# B104X.net
KiCad netlist of a schematic drawn in EAGLE
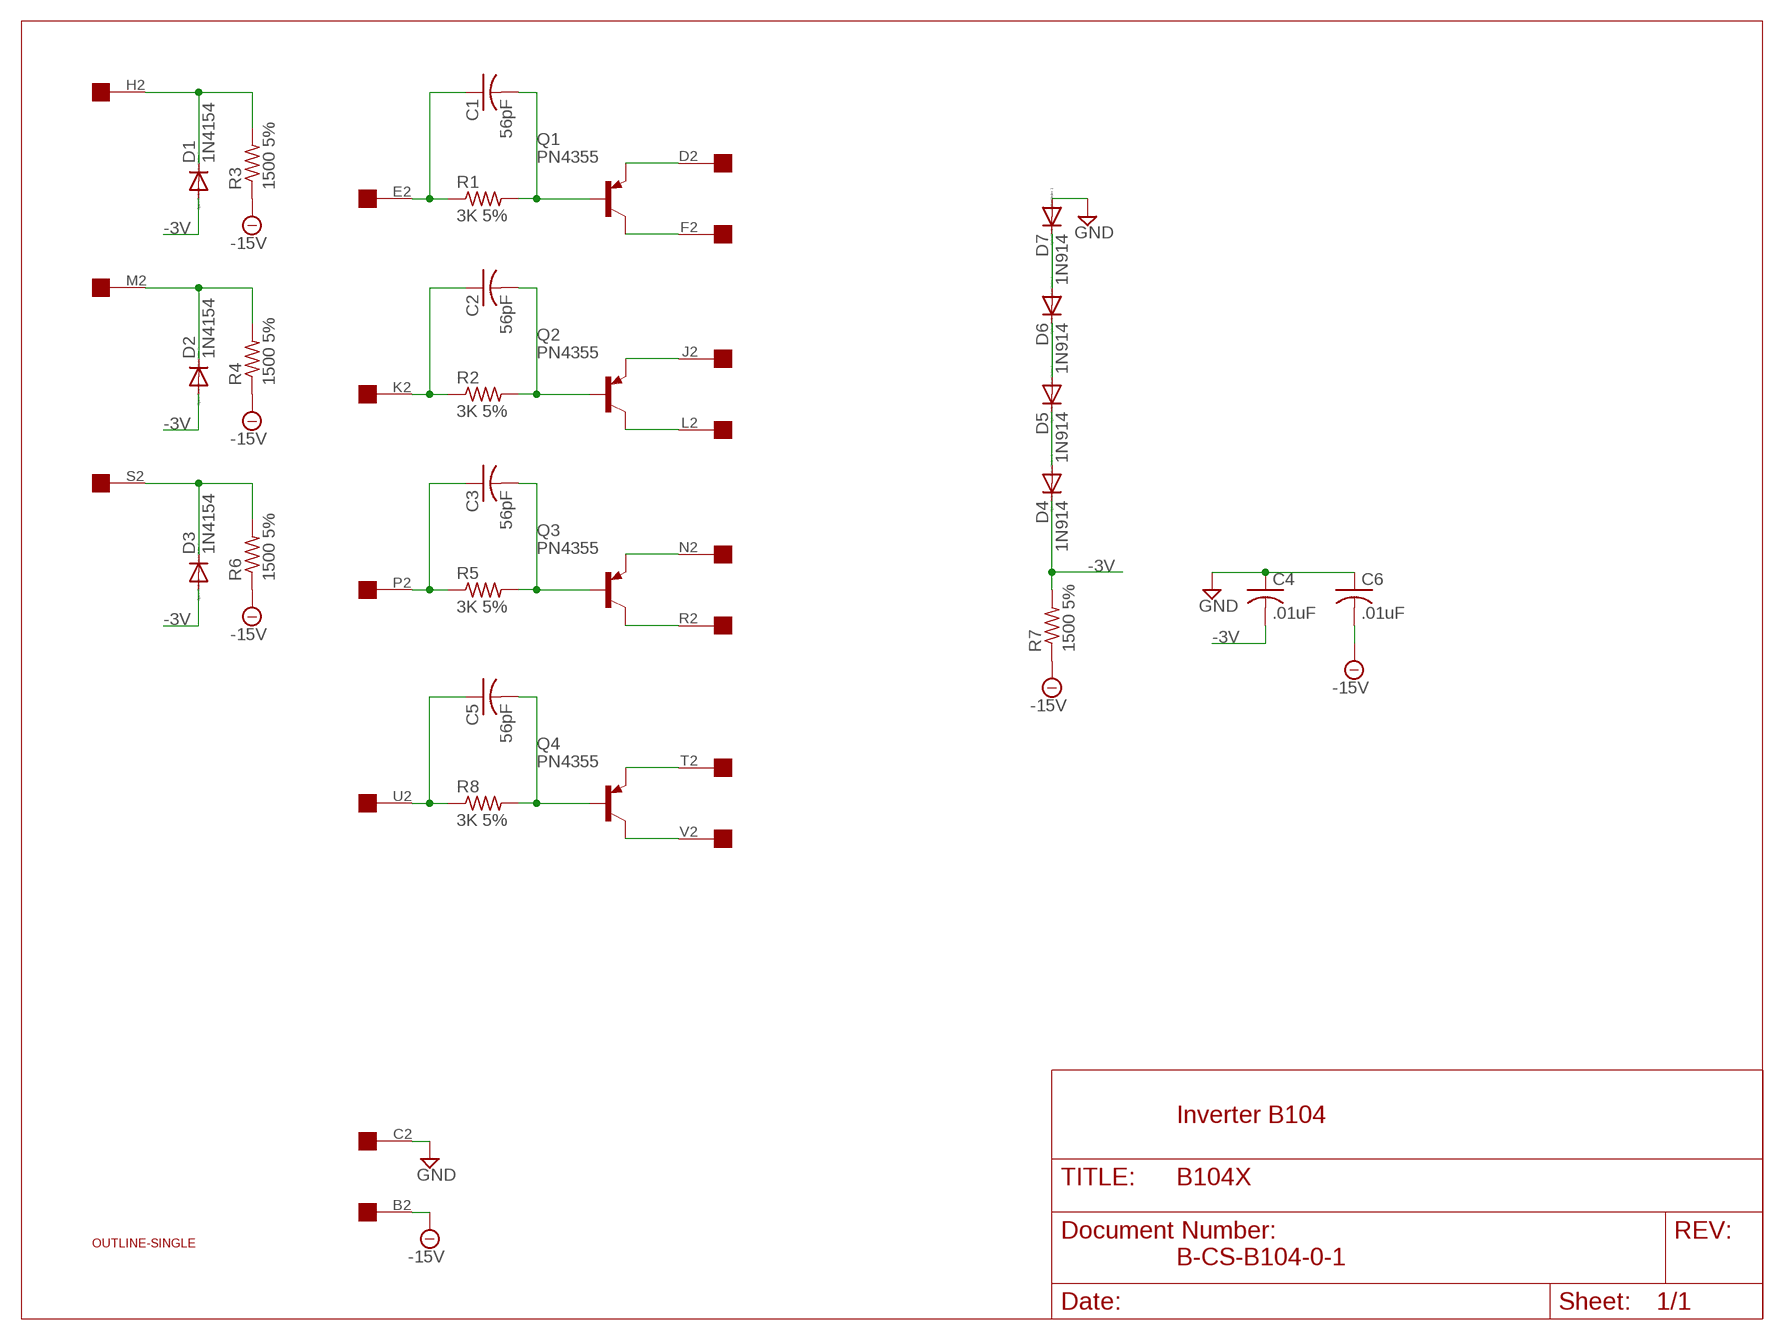
[diagram p0: schematic, sheet 1]

(export (version "E")
  (design (tool "Eeschema 10.0.6"))
  (components
    (comp (ref "C1")
      (value "56pF")
      (footprint "eagle-import:C075-032X103")
      (libsource (lib "eagle-import") (part "C-US075-032X103"))
    )
    (comp (ref "C2")
      (value "56pF")
      (footprint "eagle-import:C075-032X103")
      (libsource (lib "eagle-import") (part "C-US075-032X103"))
    )
    (comp (ref "C3")
      (value "56pF")
      (footprint "eagle-import:C075-032X103")
      (libsource (lib "eagle-import") (part "C-US075-032X103"))
    )
    (comp (ref "C4")
      (value ".01uF")
      (footprint "eagle-import:C050-025X075")
      (libsource (lib "eagle-import") (part "C-US050-025X075"))
    )
    (comp (ref "C5")
      (value "56pF")
      (footprint "eagle-import:C075-032X103")
      (libsource (lib "eagle-import") (part "C-US075-032X103"))
    )
    (comp (ref "C6")
      (value ".01uF")
      (footprint "eagle-import:C050-025X075")
      (libsource (lib "eagle-import") (part "C-US050-025X075"))
    )
    (comp (ref "D1")
      (value "1N4154")
      (footprint "eagle-import:DO35-10")
      (libsource (lib "eagle-import") (part "1N4148DO35-10"))
    )
    (comp (ref "D2")
      (value "1N4154")
      (footprint "eagle-import:DO35-10")
      (libsource (lib "eagle-import") (part "1N4148DO35-10"))
    )
    (comp (ref "D3")
      (value "1N4154")
      (footprint "eagle-import:DO35-10")
      (libsource (lib "eagle-import") (part "1N4148DO35-10"))
    )
    (comp (ref "D4")
      (value "1N914")
      (footprint "eagle-import:DO35-10")
      (libsource (lib "eagle-import") (part "1N4148DO35-10"))
    )
    (comp (ref "D5")
      (value "1N914")
      (footprint "eagle-import:DO35-10")
      (libsource (lib "eagle-import") (part "1N4148DO35-10"))
    )
    (comp (ref "D6")
      (value "1N914")
      (footprint "eagle-import:DO35-10")
      (libsource (lib "eagle-import") (part "1N4148DO35-10"))
    )
    (comp (ref "D7")
      (value "1N914")
      (footprint "eagle-import:DO35-10")
      (libsource (lib "eagle-import") (part "1N4148DO35-10"))
    )
    (comp (ref "Q1")
      (value "PN4355")
      (footprint "eagle-import:TO39")
      (libsource (lib "eagle-import") (part "2N2904"))
    )
    (comp (ref "Q2")
      (value "PN4355")
      (footprint "eagle-import:TO39")
      (libsource (lib "eagle-import") (part "2N2904"))
    )
    (comp (ref "Q3")
      (value "PN4355")
      (footprint "eagle-import:TO39")
      (libsource (lib "eagle-import") (part "2N2904"))
    )
    (comp (ref "Q4")
      (value "PN4355")
      (footprint "eagle-import:TO39")
      (libsource (lib "eagle-import") (part "2N2904"))
    )
    (comp (ref "R1")
      (value "3K 5%")
      (footprint "eagle-import:0207_10")
      (libsource (lib "eagle-import") (part "R-US_0207/10"))
    )
    (comp (ref "R2")
      (value "3K 5%")
      (footprint "eagle-import:0207_10")
      (libsource (lib "eagle-import") (part "R-US_0207/10"))
    )
    (comp (ref "R3")
      (value "1500 5%")
      (footprint "eagle-import:0207_10")
      (libsource (lib "eagle-import") (part "R-US_0207/10"))
    )
    (comp (ref "R4")
      (value "1500 5%")
      (footprint "eagle-import:0207_10")
      (libsource (lib "eagle-import") (part "R-US_0207/10"))
    )
    (comp (ref "R5")
      (value "3K 5%")
      (footprint "eagle-import:0207_10")
      (libsource (lib "eagle-import") (part "R-US_0207/10"))
    )
    (comp (ref "R6")
      (value "1500 5%")
      (footprint "eagle-import:0207_10")
      (libsource (lib "eagle-import") (part "R-US_0207/10"))
    )
    (comp (ref "R7")
      (value "1500 5%")
      (footprint "eagle-import:0207_10")
      (libsource (lib "eagle-import") (part "R-US_0207/10"))
    )
    (comp (ref "R8")
      (value "3K 5%")
      (footprint "eagle-import:0207_10")
      (libsource (lib "eagle-import") (part "R-US_0207/10"))
    )
    (comp (ref "U$1")
      (value "OUTLINE-SINGLE")
      (footprint "eagle-import:SINGLE")
      (libsource (lib "eagle-import") (part "OUTLINE-SINGLE"))
    )
    (comp (ref "U$2")
      (value "EDGE-1")
      (footprint "eagle-import:EDGE-CON1")
      (libsource (lib "eagle-import") (part "EDGE-1"))
    )
  )
  (nets
    (net (code "1") (name "-15V") (class "Default")
      (node (ref "C6") (pin "2") (pinfunction "2_2") (pintype "passive"))
      (node (ref "R3") (pin "1") (pinfunction "1_1") (pintype "passive"))
      (node (ref "R4") (pin "1") (pinfunction "1_1") (pintype "passive"))
      (node (ref "R6") (pin "1") (pinfunction "1_1") (pintype "passive"))
      (node (ref "R7") (pin "1") (pinfunction "1_1") (pintype "passive"))
      (node (ref "U$2") (pin "B2") (pinfunction "1_B2") (pintype "bidirectional"))
    )
    (net (code "2") (name "/-3V") (class "Default")
      (node (ref "C4") (pin "2") (pinfunction "2_2") (pintype "passive"))
      (node (ref "D1") (pin "A") (pinfunction "A_A") (pintype "passive"))
      (node (ref "D2") (pin "A") (pinfunction "A_A") (pintype "passive"))
      (node (ref "D3") (pin "A") (pinfunction "A_A") (pintype "passive"))
      (node (ref "D4") (pin "C") (pinfunction "C_C") (pintype "passive"))
      (node (ref "R7") (pin "2") (pinfunction "2_2") (pintype "passive"))
    )
    (net (code "3") (name "GND") (class "Default")
      (node (ref "C4") (pin "1") (pinfunction "1_1") (pintype "passive"))
      (node (ref "C6") (pin "1") (pinfunction "1_1") (pintype "passive"))
      (node (ref "D7") (pin "A") (pinfunction "A_A") (pintype "passive"))
      (node (ref "U$2") (pin "C2") (pinfunction "1_C2") (pintype "bidirectional"))
    )
    (net (code "4") (name "Net-(D4-PadA)") (class "Default")
      (node (ref "D4") (pin "A") (pinfunction "A_A") (pintype "passive"))
      (node (ref "D5") (pin "C") (pinfunction "C_C") (pintype "passive"))
    )
    (net (code "5") (name "Net-(D5-PadA)") (class "Default")
      (node (ref "D5") (pin "A") (pinfunction "A_A") (pintype "passive"))
      (node (ref "D6") (pin "C") (pinfunction "C_C") (pintype "passive"))
    )
    (net (code "6") (name "Net-(D6-PadA)") (class "Default")
      (node (ref "D6") (pin "A") (pinfunction "A_A") (pintype "passive"))
      (node (ref "D7") (pin "C") (pinfunction "C_C") (pintype "passive"))
    )
    (net (code "7") (name "Net-(Q1-B)") (class "Default")
      (node (ref "C1") (pin "2") (pinfunction "2_2") (pintype "passive"))
      (node (ref "Q1") (pin "2") (pinfunction "B_2") (pintype "passive"))
      (node (ref "R1") (pin "2") (pinfunction "2_2") (pintype "passive"))
    )
    (net (code "8") (name "Net-(Q1-C)") (class "Default")
      (node (ref "Q1") (pin "3") (pinfunction "C_3") (pintype "passive"))
      (node (ref "U$2") (pin "F2") (pinfunction "1_F2") (pintype "bidirectional"))
    )
    (net (code "9") (name "Net-(Q1-E)") (class "Default")
      (node (ref "Q1") (pin "1") (pinfunction "E_1") (pintype "passive"))
      (node (ref "U$2") (pin "D2") (pinfunction "1_D2") (pintype "bidirectional"))
    )
    (net (code "10") (name "Net-(Q2-B)") (class "Default")
      (node (ref "C2") (pin "2") (pinfunction "2_2") (pintype "passive"))
      (node (ref "Q2") (pin "2") (pinfunction "B_2") (pintype "passive"))
      (node (ref "R2") (pin "2") (pinfunction "2_2") (pintype "passive"))
    )
    (net (code "11") (name "Net-(Q2-C)") (class "Default")
      (node (ref "Q2") (pin "3") (pinfunction "C_3") (pintype "passive"))
      (node (ref "U$2") (pin "L2") (pinfunction "1_L2") (pintype "bidirectional"))
    )
    (net (code "12") (name "Net-(Q2-E)") (class "Default")
      (node (ref "Q2") (pin "1") (pinfunction "E_1") (pintype "passive"))
      (node (ref "U$2") (pin "J2") (pinfunction "1_J2") (pintype "bidirectional"))
    )
    (net (code "13") (name "Net-(Q3-B)") (class "Default")
      (node (ref "C3") (pin "2") (pinfunction "2_2") (pintype "passive"))
      (node (ref "Q3") (pin "2") (pinfunction "B_2") (pintype "passive"))
      (node (ref "R5") (pin "2") (pinfunction "2_2") (pintype "passive"))
    )
    (net (code "14") (name "Net-(Q3-C)") (class "Default")
      (node (ref "Q3") (pin "3") (pinfunction "C_3") (pintype "passive"))
      (node (ref "U$2") (pin "R2") (pinfunction "1_R2") (pintype "bidirectional"))
    )
    (net (code "15") (name "Net-(Q3-E)") (class "Default")
      (node (ref "Q3") (pin "1") (pinfunction "E_1") (pintype "passive"))
      (node (ref "U$2") (pin "N2") (pinfunction "1_N2") (pintype "bidirectional"))
    )
    (net (code "16") (name "Net-(Q4-B)") (class "Default")
      (node (ref "C5") (pin "2") (pinfunction "2_2") (pintype "passive"))
      (node (ref "Q4") (pin "2") (pinfunction "B_2") (pintype "passive"))
      (node (ref "R8") (pin "2") (pinfunction "2_2") (pintype "passive"))
    )
    (net (code "17") (name "Net-(Q4-C)") (class "Default")
      (node (ref "Q4") (pin "3") (pinfunction "C_3") (pintype "passive"))
      (node (ref "U$2") (pin "V2") (pinfunction "1_V2") (pintype "bidirectional"))
    )
    (net (code "18") (name "Net-(Q4-E)") (class "Default")
      (node (ref "Q4") (pin "1") (pinfunction "E_1") (pintype "passive"))
      (node (ref "U$2") (pin "T2") (pinfunction "1_T2") (pintype "bidirectional"))
    )
    (net (code "19") (name "Net-(U$2E-1)") (class "Default")
      (node (ref "C1") (pin "1") (pinfunction "1_1") (pintype "passive"))
      (node (ref "R1") (pin "1") (pinfunction "1_1") (pintype "passive"))
      (node (ref "U$2") (pin "E2") (pinfunction "1_E2") (pintype "bidirectional"))
    )
    (net (code "20") (name "Net-(U$2G-1)") (class "Default")
      (node (ref "D1") (pin "C") (pinfunction "C_C") (pintype "passive"))
      (node (ref "R3") (pin "2") (pinfunction "2_2") (pintype "passive"))
      (node (ref "U$2") (pin "H2") (pinfunction "1_H2") (pintype "bidirectional"))
    )
    (net (code "21") (name "Net-(U$2I-1)") (class "Default")
      (node (ref "C2") (pin "1") (pinfunction "1_1") (pintype "passive"))
      (node (ref "R2") (pin "1") (pinfunction "1_1") (pintype "passive"))
      (node (ref "U$2") (pin "K2") (pinfunction "1_K2") (pintype "bidirectional"))
    )
    (net (code "22") (name "Net-(U$2K-1)") (class "Default")
      (node (ref "D2") (pin "C") (pinfunction "C_C") (pintype "passive"))
      (node (ref "R4") (pin "2") (pinfunction "2_2") (pintype "passive"))
      (node (ref "U$2") (pin "M2") (pinfunction "1_M2") (pintype "bidirectional"))
    )
    (net (code "23") (name "Net-(U$2M-1)") (class "Default")
      (node (ref "C3") (pin "1") (pinfunction "1_1") (pintype "passive"))
      (node (ref "R5") (pin "1") (pinfunction "1_1") (pintype "passive"))
      (node (ref "U$2") (pin "P2") (pinfunction "1_P2") (pintype "bidirectional"))
    )
    (net (code "24") (name "Net-(U$2O-1)") (class "Default")
      (node (ref "D3") (pin "C") (pinfunction "C_C") (pintype "passive"))
      (node (ref "R6") (pin "2") (pinfunction "2_2") (pintype "passive"))
      (node (ref "U$2") (pin "S2") (pinfunction "1_S2") (pintype "bidirectional"))
    )
    (net (code "25") (name "Net-(U$2Q-1)") (class "Default")
      (node (ref "C5") (pin "1") (pinfunction "1_1") (pintype "passive"))
      (node (ref "R8") (pin "1") (pinfunction "1_1") (pintype "passive"))
      (node (ref "U$2") (pin "U2") (pinfunction "1_U2") (pintype "bidirectional"))
    )
  )
)
